# 24_067.net
KiCad netlist of a schematic drawn in Altium Designer
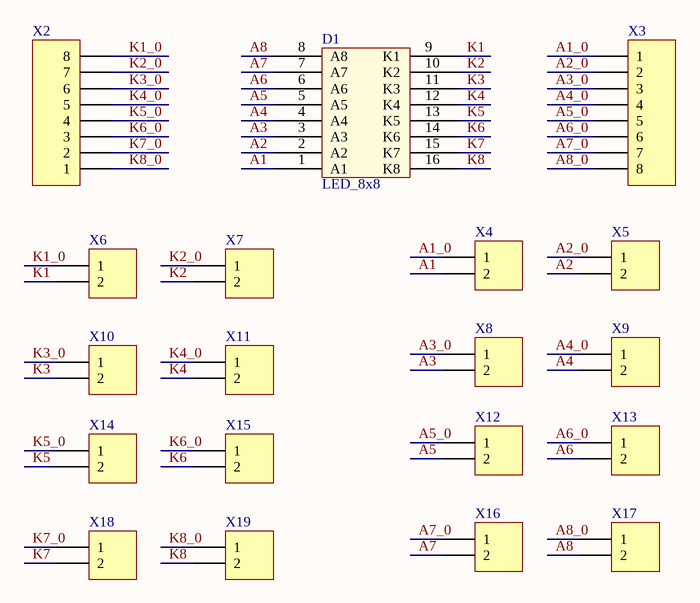
[diagram p0: 24.067.SchDoc]

(export (version "E")
  (design (tool "Eeschema 10.0.6"))
  (components
    (comp (ref "D1") (value "LED_8x8") (footprint "LED_8x8") (libsource (lib "msp_SchLib") (part "LED_8x8")))
    (comp (ref "X2")
      (value "Header 8")
      (footprint "HDR1X8")
      (description "Header, 8-Pin")
      (fields (field (name "PUBLISHER") "Altium Limited"))
      (libsource (lib "Miscellaneous Connectors") (part "Header 8"))
    )
    (comp (ref "X3")
      (value "Header 8")
      (footprint "HDR1X8")
      (description "Header, 8-Pin")
      (fields (field (name "PUBLISHER") "Altium Limited"))
      (libsource (lib "") (part "Header 8_1"))
    )
    (comp (ref "X4")
      (value "Header 2")
      (footprint "HDR1X2")
      (description "Header, 2-Pin")
      (fields (field (name "PUBLISHER") "Altium Limited"))
      (libsource (lib "Miscellaneous Connectors") (part "Header 2"))
    )
    (comp (ref "X5")
      (value "Header 2")
      (footprint "HDR1X2")
      (description "Header, 2-Pin")
      (fields (field (name "PUBLISHER") "Altium Limited"))
      (libsource (lib "Miscellaneous Connectors") (part "Header 2"))
    )
    (comp (ref "X6")
      (value "Header 2")
      (footprint "HDR1X2")
      (description "Header, 2-Pin")
      (fields (field (name "PUBLISHER") "Altium Limited"))
      (libsource (lib "Miscellaneous Connectors") (part "Header 2"))
    )
    (comp (ref "X7")
      (value "Header 2")
      (footprint "HDR1X2")
      (description "Header, 2-Pin")
      (fields (field (name "PUBLISHER") "Altium Limited"))
      (libsource (lib "Miscellaneous Connectors") (part "Header 2"))
    )
    (comp (ref "X8")
      (value "Header 2")
      (footprint "HDR1X2")
      (description "Header, 2-Pin")
      (fields (field (name "PUBLISHER") "Altium Limited"))
      (libsource (lib "Miscellaneous Connectors") (part "Header 2"))
    )
    (comp (ref "X9")
      (value "Header 2")
      (footprint "HDR1X2")
      (description "Header, 2-Pin")
      (fields (field (name "PUBLISHER") "Altium Limited"))
      (libsource (lib "Miscellaneous Connectors") (part "Header 2"))
    )
    (comp (ref "X10")
      (value "Header 2")
      (footprint "HDR1X2")
      (description "Header, 2-Pin")
      (fields (field (name "PUBLISHER") "Altium Limited"))
      (libsource (lib "Miscellaneous Connectors") (part "Header 2"))
    )
    (comp (ref "X11")
      (value "Header 2")
      (footprint "HDR1X2")
      (description "Header, 2-Pin")
      (fields (field (name "PUBLISHER") "Altium Limited"))
      (libsource (lib "Miscellaneous Connectors") (part "Header 2"))
    )
    (comp (ref "X12")
      (value "Header 2")
      (footprint "HDR1X2")
      (description "Header, 2-Pin")
      (fields (field (name "PUBLISHER") "Altium Limited"))
      (libsource (lib "Miscellaneous Connectors") (part "Header 2"))
    )
    (comp (ref "X13")
      (value "Header 2")
      (footprint "HDR1X2")
      (description "Header, 2-Pin")
      (fields (field (name "PUBLISHER") "Altium Limited"))
      (libsource (lib "Miscellaneous Connectors") (part "Header 2"))
    )
    (comp (ref "X14")
      (value "Header 2")
      (footprint "HDR1X2")
      (description "Header, 2-Pin")
      (fields (field (name "PUBLISHER") "Altium Limited"))
      (libsource (lib "Miscellaneous Connectors") (part "Header 2"))
    )
    (comp (ref "X15")
      (value "Header 2")
      (footprint "HDR1X2")
      (description "Header, 2-Pin")
      (fields (field (name "PUBLISHER") "Altium Limited"))
      (libsource (lib "Miscellaneous Connectors") (part "Header 2"))
    )
    (comp (ref "X16")
      (value "Header 2")
      (footprint "HDR1X2")
      (description "Header, 2-Pin")
      (fields (field (name "PUBLISHER") "Altium Limited"))
      (libsource (lib "Miscellaneous Connectors") (part "Header 2"))
    )
    (comp (ref "X17")
      (value "Header 2")
      (footprint "HDR1X2")
      (description "Header, 2-Pin")
      (fields (field (name "PUBLISHER") "Altium Limited"))
      (libsource (lib "Miscellaneous Connectors") (part "Header 2"))
    )
    (comp (ref "X18")
      (value "Header 2")
      (footprint "HDR1X2")
      (description "Header, 2-Pin")
      (fields (field (name "PUBLISHER") "Altium Limited"))
      (libsource (lib "Miscellaneous Connectors") (part "Header 2"))
    )
    (comp (ref "X19")
      (value "Header 2")
      (footprint "HDR1X2")
      (description "Header, 2-Pin")
      (fields (field (name "PUBLISHER") "Altium Limited"))
      (libsource (lib "Miscellaneous Connectors") (part "Header 2"))
    )
  )
  (nets
    (net (code "1") (name "/A1") (class "Default")
      (node (ref "D1") (pin "1") (pinfunction "A1_1") (pintype "passive"))
      (node (ref "X4") (pin "2") (pinfunction "2_2") (pintype "passive"))
    )
    (net (code "2") (name "/A1_0") (class "Default")
      (node (ref "X3") (pin "1") (pinfunction "1_1") (pintype "passive"))
      (node (ref "X4") (pin "1") (pinfunction "1_1") (pintype "passive"))
    )
    (net (code "3") (name "/A2") (class "Default")
      (node (ref "D1") (pin "2") (pinfunction "A2_2") (pintype "passive"))
      (node (ref "X5") (pin "2") (pinfunction "2_2") (pintype "passive"))
    )
    (net (code "4") (name "/A2_0") (class "Default")
      (node (ref "X3") (pin "2") (pinfunction "2_2") (pintype "passive"))
      (node (ref "X5") (pin "1") (pinfunction "1_1") (pintype "passive"))
    )
    (net (code "5") (name "/A3") (class "Default")
      (node (ref "D1") (pin "3") (pinfunction "A3_3") (pintype "passive"))
      (node (ref "X8") (pin "2") (pinfunction "2_2") (pintype "passive"))
    )
    (net (code "6") (name "/A3_0") (class "Default")
      (node (ref "X3") (pin "3") (pinfunction "3_3") (pintype "passive"))
      (node (ref "X8") (pin "1") (pinfunction "1_1") (pintype "passive"))
    )
    (net (code "7") (name "/A4") (class "Default")
      (node (ref "D1") (pin "4") (pinfunction "A4_4") (pintype "passive"))
      (node (ref "X9") (pin "2") (pinfunction "2_2") (pintype "passive"))
    )
    (net (code "8") (name "/A4_0") (class "Default")
      (node (ref "X3") (pin "4") (pinfunction "4_4") (pintype "passive"))
      (node (ref "X9") (pin "1") (pinfunction "1_1") (pintype "passive"))
    )
    (net (code "9") (name "/A5") (class "Default")
      (node (ref "D1") (pin "5") (pinfunction "A5_5") (pintype "passive"))
      (node (ref "X12") (pin "2") (pinfunction "2_2") (pintype "passive"))
    )
    (net (code "10") (name "/A5_0") (class "Default")
      (node (ref "X12") (pin "1") (pinfunction "1_1") (pintype "passive"))
      (node (ref "X3") (pin "5") (pinfunction "5_5") (pintype "passive"))
    )
    (net (code "11") (name "/A6") (class "Default")
      (node (ref "D1") (pin "6") (pinfunction "A6_6") (pintype "passive"))
      (node (ref "X13") (pin "2") (pinfunction "2_2") (pintype "passive"))
    )
    (net (code "12") (name "/A6_0") (class "Default")
      (node (ref "X13") (pin "1") (pinfunction "1_1") (pintype "passive"))
      (node (ref "X3") (pin "6") (pinfunction "6_6") (pintype "passive"))
    )
    (net (code "13") (name "/A7") (class "Default")
      (node (ref "D1") (pin "7") (pinfunction "A7_7") (pintype "passive"))
      (node (ref "X16") (pin "2") (pinfunction "2_2") (pintype "passive"))
    )
    (net (code "14") (name "/A7_0") (class "Default")
      (node (ref "X16") (pin "1") (pinfunction "1_1") (pintype "passive"))
      (node (ref "X3") (pin "7") (pinfunction "7_7") (pintype "passive"))
    )
    (net (code "15") (name "/A8") (class "Default")
      (node (ref "D1") (pin "8") (pinfunction "A8_8") (pintype "passive"))
      (node (ref "X17") (pin "2") (pinfunction "2_2") (pintype "passive"))
    )
    (net (code "16") (name "/A8_0") (class "Default")
      (node (ref "X17") (pin "1") (pinfunction "1_1") (pintype "passive"))
      (node (ref "X3") (pin "8") (pinfunction "8_8") (pintype "passive"))
    )
    (net (code "17") (name "/K1") (class "Default")
      (node (ref "D1") (pin "9") (pinfunction "K1_9") (pintype "passive"))
      (node (ref "X6") (pin "2") (pinfunction "2_2") (pintype "passive"))
    )
    (net (code "18") (name "/K1_0") (class "Default")
      (node (ref "X2") (pin "8") (pinfunction "8_8") (pintype "passive"))
      (node (ref "X6") (pin "1") (pinfunction "1_1") (pintype "passive"))
    )
    (net (code "19") (name "/K2") (class "Default")
      (node (ref "D1") (pin "10") (pinfunction "K2_10") (pintype "passive"))
      (node (ref "X7") (pin "2") (pinfunction "2_2") (pintype "passive"))
    )
    (net (code "20") (name "/K2_0") (class "Default")
      (node (ref "X2") (pin "7") (pinfunction "7_7") (pintype "passive"))
      (node (ref "X7") (pin "1") (pinfunction "1_1") (pintype "passive"))
    )
    (net (code "21") (name "/K3") (class "Default")
      (node (ref "D1") (pin "11") (pinfunction "K3_11") (pintype "passive"))
      (node (ref "X10") (pin "2") (pinfunction "2_2") (pintype "passive"))
    )
    (net (code "22") (name "/K3_0") (class "Default")
      (node (ref "X10") (pin "1") (pinfunction "1_1") (pintype "passive"))
      (node (ref "X2") (pin "6") (pinfunction "6_6") (pintype "passive"))
    )
    (net (code "23") (name "/K4") (class "Default")
      (node (ref "D1") (pin "12") (pinfunction "K4_12") (pintype "passive"))
      (node (ref "X11") (pin "2") (pinfunction "2_2") (pintype "passive"))
    )
    (net (code "24") (name "/K4_0") (class "Default")
      (node (ref "X11") (pin "1") (pinfunction "1_1") (pintype "passive"))
      (node (ref "X2") (pin "5") (pinfunction "5_5") (pintype "passive"))
    )
    (net (code "25") (name "/K5") (class "Default")
      (node (ref "D1") (pin "13") (pinfunction "K5_13") (pintype "passive"))
      (node (ref "X14") (pin "2") (pinfunction "2_2") (pintype "passive"))
    )
    (net (code "26") (name "/K5_0") (class "Default")
      (node (ref "X14") (pin "1") (pinfunction "1_1") (pintype "passive"))
      (node (ref "X2") (pin "4") (pinfunction "4_4") (pintype "passive"))
    )
    (net (code "27") (name "/K6") (class "Default")
      (node (ref "D1") (pin "14") (pinfunction "K6_14") (pintype "passive"))
      (node (ref "X15") (pin "2") (pinfunction "2_2") (pintype "passive"))
    )
    (net (code "28") (name "/K6_0") (class "Default")
      (node (ref "X15") (pin "1") (pinfunction "1_1") (pintype "passive"))
      (node (ref "X2") (pin "3") (pinfunction "3_3") (pintype "passive"))
    )
    (net (code "29") (name "/K7") (class "Default")
      (node (ref "D1") (pin "15") (pinfunction "K7_15") (pintype "passive"))
      (node (ref "X18") (pin "2") (pinfunction "2_2") (pintype "passive"))
    )
    (net (code "30") (name "/K7_0") (class "Default")
      (node (ref "X18") (pin "1") (pinfunction "1_1") (pintype "passive"))
      (node (ref "X2") (pin "2") (pinfunction "2_2") (pintype "passive"))
    )
    (net (code "31") (name "/K8") (class "Default")
      (node (ref "D1") (pin "16") (pinfunction "K8_16") (pintype "passive"))
      (node (ref "X19") (pin "2") (pinfunction "2_2") (pintype "passive"))
    )
    (net (code "32") (name "/K8_0") (class "Default")
      (node (ref "X19") (pin "1") (pinfunction "1_1") (pintype "passive"))
      (node (ref "X2") (pin "1") (pinfunction "1_1") (pintype "passive"))
    )
  )
)
